# PWR_5to-5_MAX755.net
KiCad netlist of a schematic drawn in Altium Designer
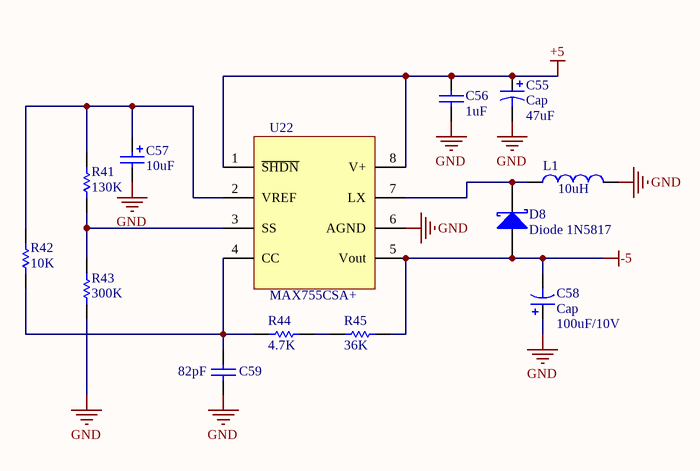
[diagram p0: PWR_5to-5_MAX755.SchDoc]

(export (version "E")
  (design (tool "Eeschema 10.0.6"))
  (components
    (comp (ref "C55")
      (value "Cap")
      (footprint "1206(pol)")
      (description "Polarized Capacitor (Radial)")
      (fields (field (name "ALTIUM_VALUE") "47uF") (field (name "PUBLISHER") "Altium Limited"))
      (libsource (lib "Miscellaneous Devices") (part "Cap Pol1"))
    )
    (comp (ref "C56")
      (value "1uF")
      (footprint "C1206")
      (description "Capacitor")
      (fields (field (name "Comment") "Cap") (field (name "PUBLISHER") "Altium Limited"))
      (libsource (lib "SIGNALPRO") (part "Cap"))
    )
    (comp (ref "C57")
      (value "10uF")
      (footprint "1206(pol)")
      (description "Polarized Capacitor (Radial)")
      (fields (field (name "Comment") "Cap Pol") (field (name "PUBLISHER") "Altium Limited"))
      (libsource (lib "SIGNALPRO") (part "Cap Pol"))
    )
    (comp (ref "C58")
      (value "Cap")
      (footprint "1206(pol)")
      (description "Polarized Capacitor (Radial)")
      (fields (field (name "ALTIUM_VALUE") "100uF/10V") (field (name "PUBLISHER") "Altium Limited"))
      (libsource (lib "Miscellaneous Devices") (part "Cap Pol1"))
    )
    (comp (ref "C59")
      (value "82pF")
      (footprint "C1206")
      (description "Capacitor")
      (fields (field (name "Comment") "Cap") (field (name "PUBLISHER") "Altium Limited"))
      (libsource (lib "SIGNALPRO") (part "Cap"))
    )
    (comp (ref "D8")
      (value "Diode 1N5817")
      (footprint "DIODE-SMA")
      (description "Schottky Rectifier")
      (fields (field (name "PUBLISHER") "Altium Limited"))
      (libsource (lib "Miscellaneous Devices") (part "Diode 10TQ045"))
    )
    (comp (ref "L1")
      (value "10uH")
      (footprint "1210")
      (description "Inductor")
      (fields (field (name "Comment") "Inductor(1210)") (field (name "PUBLISHER") "Altium Limited"))
      (libsource (lib "SIGNALPRO") (part "Inductor(1210)"))
    )
    (comp (ref "R41")
      (value "130K")
      (footprint "1206")
      (description "Resistor")
      (fields (field (name "Comment") "Res") (field (name "PUBLISHER") "Altium Limited"))
      (libsource (lib "SIGNALPRO") (part "Res1206"))
    )
    (comp (ref "R42")
      (value "10K")
      (footprint "1206")
      (description "Resistor")
      (fields (field (name "Comment") "Res") (field (name "PUBLISHER") "Altium Limited"))
      (libsource (lib "SIGNALPRO") (part "Res1206"))
    )
    (comp (ref "R43")
      (value "300K")
      (footprint "1206")
      (description "Resistor")
      (fields (field (name "Comment") "Res") (field (name "PUBLISHER") "Altium Limited"))
      (libsource (lib "SIGNALPRO") (part "Res1206"))
    )
    (comp (ref "R44")
      (value "4.7K")
      (footprint "1206")
      (description "Resistor")
      (fields (field (name "Comment") "Res") (field (name "PUBLISHER") "Altium Limited"))
      (libsource (lib "SIGNALPRO") (part "Res1206"))
    )
    (comp (ref "R45")
      (value "36K")
      (footprint "1206")
      (description "Resistor")
      (fields (field (name "Comment") "Res") (field (name "PUBLISHER") "Altium Limited"))
      (libsource (lib "SIGNALPRO") (part "Res1206"))
    )
    (comp (ref "U22")
      (value "MAX755CSA+")
      (footprint "SOIC-8")
      (description "VOLTAGE INVERTING")
      (libsource (lib "SIGNALPRO") (part "MAX755CSA+"))
    )
  )
  (nets
    (net (code "1") (name "+5") (class "Default")
      (node (ref "C55") (pin "1") (pinfunction "1_1") (pintype "passive"))
      (node (ref "C56") (pin "2") (pinfunction "2_2") (pintype "passive"))
      (node (ref "U22") (pin "1") (pinfunction "~{SHDN}_1") (pintype "passive"))
      (node (ref "U22") (pin "8") (pinfunction "V+_8") (pintype "passive"))
    )
    (net (code "2") (name "-5") (class "Default")
      (node (ref "C58") (pin "2") (pinfunction "2_2") (pintype "passive"))
      (node (ref "D8") (pin "3") (pinfunction "A_3") (pintype "passive"))
      (node (ref "R45") (pin "1") (pinfunction "1_1") (pintype "passive"))
      (node (ref "U22") (pin "5") (pinfunction "Vout_5") (pintype "passive"))
    )
    (net (code "3") (name "GND") (class "Default")
      (node (ref "C55") (pin "2") (pinfunction "2_2") (pintype "passive"))
      (node (ref "C56") (pin "1") (pinfunction "1_1") (pintype "passive"))
      (node (ref "C57") (pin "2") (pinfunction "2_2") (pintype "passive"))
      (node (ref "C58") (pin "1") (pinfunction "1_1") (pintype "passive"))
      (node (ref "C59") (pin "1") (pinfunction "1_1") (pintype "passive"))
      (node (ref "L1") (pin "2") (pinfunction "2_2") (pintype "passive"))
      (node (ref "R43") (pin "1") (pinfunction "1_1") (pintype "passive"))
      (node (ref "U22") (pin "6") (pinfunction "AGND_6") (pintype "passive"))
    )
    (net (code "4") (name "Net-(D8-K)") (class "Default")
      (node (ref "D8") (pin "1") (pinfunction "K_1") (pintype "passive"))
      (node (ref "L1") (pin "1") (pinfunction "1_1") (pintype "passive"))
      (node (ref "U22") (pin "7") (pinfunction "LX_7") (pintype "passive"))
    )
    (net (code "5") (name "Net-(R44-Pad1)") (class "Default")
      (node (ref "R44") (pin "1") (pinfunction "1_1") (pintype "passive"))
      (node (ref "R45") (pin "2") (pinfunction "2_2") (pintype "passive"))
    )
    (net (code "6") (name "Net-(U22-CC)") (class "Default")
      (node (ref "C59") (pin "2") (pinfunction "2_2") (pintype "passive"))
      (node (ref "R42") (pin "1") (pinfunction "1_1") (pintype "passive"))
      (node (ref "R44") (pin "2") (pinfunction "2_2") (pintype "passive"))
      (node (ref "U22") (pin "4") (pinfunction "CC_4") (pintype "passive"))
    )
    (net (code "7") (name "Net-(U22-SS)") (class "Default")
      (node (ref "R41") (pin "1") (pinfunction "1_1") (pintype "passive"))
      (node (ref "R43") (pin "2") (pinfunction "2_2") (pintype "passive"))
      (node (ref "U22") (pin "3") (pinfunction "SS_3") (pintype "passive"))
    )
    (net (code "8") (name "Net-(U22-VREF)") (class "Default")
      (node (ref "C57") (pin "1") (pinfunction "1_1") (pintype "passive"))
      (node (ref "R41") (pin "2") (pinfunction "2_2") (pintype "passive"))
      (node (ref "R42") (pin "2") (pinfunction "2_2") (pintype "passive"))
      (node (ref "U22") (pin "2") (pinfunction "VREF_2") (pintype "passive"))
    )
  )
)
